# Power-Sheet-2.net
KiCad netlist of a schematic drawn in Altium Designer
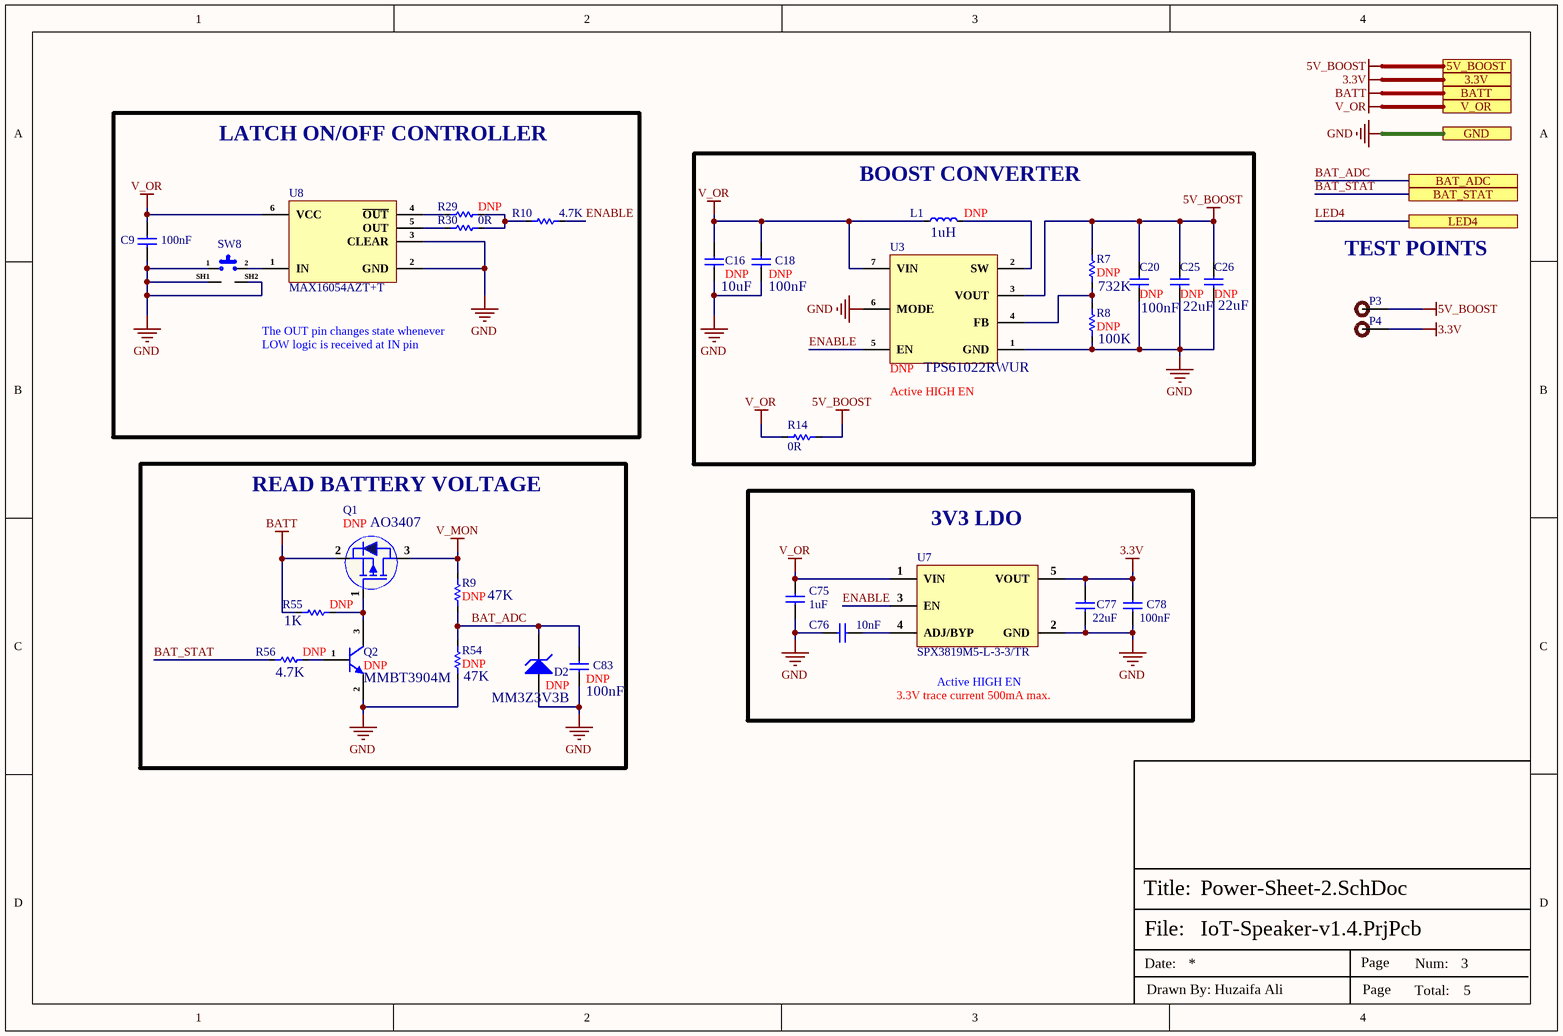
[diagram p0: Power-Sheet-2.SchDoc]

(export (version "E")
  (design (tool "Eeschema 10.0.6"))
  (components
    (comp (ref "C9")
      (value "100nF")
      (footprint "Cap-0402")
      (description "CAP CER 0.1UF 25V X5R 0402")
      (fields
        (field (name "MANUFACTURER") "Yageo")
        (field (name "MANUFACTURER PART NUMBER") "CC0402KRX5R8BB104")
      )
      (libsource (lib "eSpark_centralized_Library(2022)") (part "CC0402KRX5R8BB104"))
    )
    (comp (ref "C16")
      (value "DNP")
      (footprint "Cap-0805")
      (description "CAP CER 10UF 25V X5R 0805")
      (fields
        (field (name "MANUFACTURER") "Yageo")
        (field (name "MANUFACTURER PART NUMBER") "CC0805KKX5R8BB106")
      )
      (libsource (lib "eSpark_centralized_Library(2022)") (part "CC0805KKX5R8BB106"))
    )
    (comp (ref "C18")
      (value "DNP")
      (footprint "Cap-0402")
      (description "CAP CER 0.1UF 25V X5R 0402")
      (fields
        (field (name "MANUFACTURER") "Yageo")
        (field (name "MANUFACTURER PART NUMBER") "CC0402KRX5R8BB104")
      )
      (libsource (lib "eSpark_centralized_Library(2022)") (part "CC0402KRX5R8BB104"))
    )
    (comp (ref "C20")
      (value "DNP")
      (footprint "Cap-0402")
      (description "CAP CER 0.1UF 25V X5R 0402")
      (fields
        (field (name "MANUFACTURER") "Yageo")
        (field (name "MANUFACTURER PART NUMBER") "CC0402KRX5R8BB104")
      )
      (libsource (lib "eSpark_centralized_Library(2022)") (part "CC0402KRX5R8BB104"))
    )
    (comp (ref "C25")
      (value "DNP")
      (footprint "Cap-0603")
      (description "CAP CER 22UF 10V X5R 0603")
      (fields
        (field (name "MANUFACTURER") "Yageo")
        (field (name "MANUFACTURER PART NUMBER") "CC0603MRX5R6BB226")
      )
      (libsource (lib "eSpark_centralized_Library(2022)") (part "CC0603MRX5R6BB226"))
    )
    (comp (ref "C26")
      (value "DNP")
      (footprint "Cap-0603")
      (description "CAP CER 22UF 10V X5R 0603")
      (fields
        (field (name "MANUFACTURER") "Yageo")
        (field (name "MANUFACTURER PART NUMBER") "CC0603MRX5R6BB226")
      )
      (libsource (lib "eSpark_centralized_Library(2022)") (part "CC0603MRX5R6BB226"))
    )
    (comp (ref "C75")
      (value "1uF")
      (footprint "Cap-0603")
      (description "CAP CER 1UF 25V X5R 0603")
      (fields
        (field (name "MANUFACTURER") "Yageo")
        (field (name "MANUFACTURER PART NUMBER") "CC0603KRX5R8BB105")
      )
      (libsource (lib "eSpark_centralized_Library(2022)") (part "CC0603KRX5R8BB105"))
    )
    (comp (ref "C76")
      (value "10nF")
      (footprint "Cap-0603")
      (description "CAP CER 10000PF 50V C0G/NPO 0603")
      (fields
        (field (name "MANUFACTURER") "Yageo")
        (field (name "MANUFACTURER PART NUMBER") "CC0603JRNPO9BN103")
      )
      (libsource (lib "eSpark_centralized_Library(2022)") (part "CC0603JRNPO9BN103"))
    )
    (comp (ref "C77")
      (value "22uF")
      (footprint "Cap-0603")
      (description "CAP CER 22UF 10V X5R 0603")
      (fields
        (field (name "MANUFACTURER") "Yageo")
        (field (name "MANUFACTURER PART NUMBER") "CC0603MRX5R6BB226")
      )
      (libsource (lib "eSpark_centralized_Library(2022)") (part "CC0603MRX5R6BB226"))
    )
    (comp (ref "C78")
      (value "100nF")
      (footprint "Cap-0402")
      (description "CAP CER 0.1UF 25V X5R 0402")
      (fields
        (field (name "MANUFACTURER") "Yageo")
        (field (name "MANUFACTURER PART NUMBER") "CC0402KRX5R8BB104")
      )
      (libsource (lib "eSpark_centralized_Library(2022)") (part "CC0402KRX5R8BB104"))
    )
    (comp (ref "C83")
      (value "DNP")
      (footprint "Cap-0402")
      (description "CAP CER 0.1UF 25V X5R 0402")
      (fields
        (field (name "MANUFACTURER") "Yageo")
        (field (name "MANUFACTURER PART NUMBER") "CC0402KRX5R8BB104")
      )
      (libsource (lib "eSpark_centralized_Library(2022)") (part "CC0402KRX5R8BB104"))
    )
    (comp (ref "D2")
      (value "DNP")
      (footprint "SOD323F")
      (description "DIODE ZENER 3.3V 200MW SOD323F")
      (fields
        (field (name "MANUFACTURER") "ON Semiconductor / Fairchild")
        (field (name "MANUFACTURER PART NUMBER") "MM3Z3V3B")
      )
      (libsource (lib "eSpark_centralized_Library(2022)") (part "MM3Z3V3B"))
    )
    (comp (ref "L1")
      (value "DNP")
      (footprint "MPIT6045-1R0N-LF")
      (description "5.15A 1uH ±30% SMD Power Inductors ROHS")
      (fields
        (field (name "MANUFACTURER") "microgate")
        (field (name "MANUFACTURER PART NUMBER") "MPIT6045-1R0N-LF")
      )
      (libsource (lib "eSpark_centralized_Library(2022)") (part "MPIT6045-1R0N-LF"))
    )
    (comp (ref "P3")
      (value "TEST POINT")
      (footprint "Test-point")
      (description "Test Point ON")
      (libsource (lib "eSpark_centralized_Library(2022)") (part "TEST POINT"))
    )
    (comp (ref "P4")
      (value "TEST POINT")
      (footprint "Test-point")
      (description "Test Point ON")
      (libsource (lib "eSpark_centralized_Library(2022)") (part "TEST POINT"))
    )
    (comp (ref "Q1")
      (value "DNP")
      (footprint "SOT-23")
      (description "30V 4.1A 60mΩ@10V,4.1A 350mW 3V@250uA P Channel SOT-23 MOSFETs ROHS")
      (fields
        (field (name "MANUFACTURER") "Guangdong Hottech")
        (field (name "MANUFACTURER PART NUMBER") "AO3407")
      )
      (libsource (lib "eSpark_centralized_Library(2022)") (part "AO3407"))
    )
    (comp (ref "Q2")
      (value "DNP")
      (footprint "SOT-723")
      (fields
        (field (name "MANUFACTURER") "TECH PUBLIC")
        (field (name "MANUFACTURER PART NUMBER") "MMBT3904M")
        (field (name "LCSC PART NUMBER") "C2923360")
      )
      (libsource (lib "eSpark_centralized_Library(2022)") (part "MMBT3904M"))
    )
    (comp (ref "R7")
      (value "DNP")
      (footprint "Res-0402")
      (description "±1% 732kΩ 0402 Chip Resistor - Surface Mount ROHS")
      (fields
        (field (name "MANUFACTURER") "FOJAN")
        (field (name "MANUFACTURER PART NUMBER") "FRC0402F7323TS")
      )
      (libsource (lib "eSpark_centralized_Library(2022)") (part "FRC0402F7323TS"))
    )
    (comp (ref "R8")
      (value "DNP")
      (footprint "Res-0603")
      (description "RES SMD 100K OHM 0.1% 1/10W 0603")
      (fields
        (field (name "MANUFACTURER") "Yageo")
        (field (name "MANUFACTURER PART NUMBER") "RT0603BRD07100KL")
      )
      (libsource (lib "eSpark_centralized_Library(2022)") (part "RT0603BRD07100KL"))
    )
    (comp (ref "R9")
      (value "DNP")
      (footprint "Res-0603")
      (description "RES 47K OHM 5% 1/10W 0603")
      (fields
        (field (name "MANUFACTURER") "Yageo")
        (field (name "MANUFACTURER PART NUMBER") "RC0603JR-0747KL")
      )
      (libsource (lib "eSpark_centralized_Library(2022)") (part "RC0603JR-0747KL"))
    )
    (comp (ref "R10")
      (value "4.7K")
      (footprint "Res-0603")
      (description "RES SMD 4.7K OHM 5% 1/10W 0603")
      (fields
        (field (name "MANUFACTURER") "Yageo")
        (field (name "MANUFACTURER PART NUMBER") "RC0603JR-074K7L")
      )
      (libsource (lib "eSpark Libraries") (part "RC0603JR-074K7L"))
    )
    (comp (ref "R14")
      (value "0R")
      (footprint "Res-0603")
      (description "RES 0 OHM JUMPER 1/10W 0603")
      (fields
        (field (name "MANUFACTURER") "Yageo")
        (field (name "MANUFACTURER PART NUMBER") "RC0603JR-070RL")
      )
      (libsource (lib "eSpark Libraries") (part "RC0603JR-070RL"))
    )
    (comp (ref "R29")
      (value "DNP")
      (footprint "Res-0603")
      (description "RES SMD 0R, 1%, 0.1W, 0603")
      (fields
        (field (name "MANUFACTURER") "Yageo")
        (field (name "MANUFACTURER PART NUMBER") "RC0603FR-070RL")
      )
      (libsource (lib "eSpark Libraries") (part "RC0603FR-070RL"))
    )
    (comp (ref "R30")
      (value "0R")
      (footprint "Res-0603")
      (description "RES SMD 0R, 1%, 0.1W, 0603")
      (fields
        (field (name "MANUFACTURER") "Yageo")
        (field (name "MANUFACTURER PART NUMBER") "RC0603FR-070RL")
      )
      (libsource (lib "eSpark Libraries") (part "RC0603FR-070RL"))
    )
    (comp (ref "R54")
      (value "DNP")
      (footprint "Res-0603")
      (description "RES 47K OHM 5% 1/10W 0603")
      (fields
        (field (name "MANUFACTURER") "Yageo")
        (field (name "MANUFACTURER PART NUMBER") "RC0603JR-0747KL")
      )
      (libsource (lib "eSpark_centralized_Library(2022)") (part "RC0603JR-0747KL"))
    )
    (comp (ref "R55")
      (value "DNP")
      (footprint "Res-0603")
      (description "RES SMD 1K OHM 1% 1/10W 0603")
      (fields
        (field (name "MANUFACTURER") "Yageo")
        (field (name "MANUFACTURER PART NUMBER") "RC0603FR-071KL")
      )
      (libsource (lib "eSpark_centralized_Library(2022)") (part "RC0603FR-071KL"))
    )
    (comp (ref "R56")
      (value "DNP")
      (footprint "Res-0603")
      (description "RES SMD 4.7K OHM 5% 1/10W 0603")
      (fields
        (field (name "MANUFACTURER") "Yageo")
        (field (name "MANUFACTURER PART NUMBER") "RC0603JR-074K7L")
      )
      (libsource (lib "eSpark_centralized_Library(2022)") (part "RC0603JR-074K7L"))
    )
    (comp (ref "SW8")
      (value "TS-1087E-B3D2")
      (footprint "TS-1087E-B3D2")
      (description "Plugin-4P,7.7x3.5mm Tactile Switches ROHS")
      (fields (field (name "MANUFACTURER") "Yuandi") (field (name "LCSC PART NUMBER") "C541963"))
      (libsource (lib "eSpark Libraries") (part "TS-1087E-B3D2"))
    )
    (comp (ref "U3")
      (value "DNP")
      (footprint "7-VQFN-HR (2x2)")
      (description "8-A boost converter with 0.5-V ultra-low input voltage 7-VQFN-HR -40 to 125")
      (fields
        (field (name "MANUFACTURER") "Texas Instruments")
        (field (name "MANUFACTURER PART NUMBER") "TPS61022RWUR")
      )
      (libsource (lib "Centralize") (part "TPS61022RWUR"))
    )
    (comp (ref "U7")
      (value "SPX3819M5-L-3-3/TR")
      (footprint "SOT-23-5")
      (description "SPX3819 Series 3.3 V 500 mA Fixed Output SMT LDO Regulator - SOT-23-5")
      (fields (field (name "MANUFACTURER") "MaxLinear") (field (name "LCSC PART NUMBER") "C9055"))
      (libsource (lib "eSpark_centralized_Library(2022)") (part "SPX3819M5-L-3-3/TR"))
    )
    (comp (ref "U8")
      (value "MAX16054AZT+T")
      (footprint "TSOT-23-6")
      (description "IC CNTRLR ON/OFF W/DEB TSOT23-6")
      (fields (field (name "MANUFACTURER") "Maxim") (field (name "LCSC PART NUMBER") "C79401"))
      (libsource (lib "eSpark_centralized_Library(2022)") (part "MAX16054AZT+T"))
    )
  )
  (nets
    (net (code "1") (name "/BAT_ADC") (class "Default")
      (node (ref "C83") (pin "2") (pinfunction "2_2") (pintype "passive"))
      (node (ref "D2") (pin "2") (pinfunction "K_2") (pintype "passive"))
      (node (ref "R54") (pin "2") (pinfunction "2_2") (pintype "passive"))
      (node (ref "R9") (pin "1") (pinfunction "1_1") (pintype "passive"))
    )
    (net (code "2") (name "/BAT_STAT") (class "Default")
      (node (ref "R56") (pin "1") (pinfunction "1_1") (pintype "passive"))
    )
    (net (code "3") (name "/ENABLE") (class "Default")
      (node (ref "R10") (pin "2") (pinfunction "2_2") (pintype "passive"))
      (node (ref "U3") (pin "5") (pinfunction "EN_5") (pintype "passive"))
      (node (ref "U7") (pin "3") (pinfunction "EN_3") (pintype "passive"))
    )
    (net (code "5") (name "3.3V") (class "Default")
      (node (ref "C77") (pin "2") (pinfunction "2_2") (pintype "passive"))
      (node (ref "C78") (pin "2") (pinfunction "2_2") (pintype "passive"))
      (node (ref "P4") (pin "1") (pinfunction "1_1") (pintype "passive"))
      (node (ref "U7") (pin "5") (pinfunction "VOUT_5") (pintype "passive"))
    )
    (net (code "6") (name "5V_BOOST") (class "Default")
      (node (ref "C20") (pin "2") (pinfunction "2_2") (pintype "passive"))
      (node (ref "C25") (pin "2") (pinfunction "2_2") (pintype "passive"))
      (node (ref "C26") (pin "2") (pinfunction "2_2") (pintype "passive"))
      (node (ref "P3") (pin "1") (pinfunction "1_1") (pintype "passive"))
      (node (ref "R14") (pin "2") (pinfunction "2_2") (pintype "passive"))
      (node (ref "R7") (pin "2") (pinfunction "2_2") (pintype "passive"))
      (node (ref "U3") (pin "3") (pinfunction "VOUT_3") (pintype "passive"))
    )
    (net (code "7") (name "BATT") (class "Default")
      (node (ref "Q1") (pin "2") (pinfunction "S_2") (pintype "passive"))
      (node (ref "R55") (pin "1") (pinfunction "1_1") (pintype "passive"))
    )
    (net (code "8") (name "GND") (class "Default")
      (node (ref "C16") (pin "1") (pinfunction "1_1") (pintype "passive"))
      (node (ref "C18") (pin "1") (pinfunction "1_1") (pintype "passive"))
      (node (ref "C20") (pin "1") (pinfunction "1_1") (pintype "passive"))
      (node (ref "C25") (pin "1") (pinfunction "1_1") (pintype "passive"))
      (node (ref "C26") (pin "1") (pinfunction "1_1") (pintype "passive"))
      (node (ref "C75") (pin "1") (pinfunction "1_1") (pintype "passive"))
      (node (ref "C76") (pin "1") (pinfunction "1_1") (pintype "passive"))
      (node (ref "C77") (pin "1") (pinfunction "1_1") (pintype "passive"))
      (node (ref "C78") (pin "1") (pinfunction "1_1") (pintype "passive"))
      (node (ref "C83") (pin "1") (pinfunction "1_1") (pintype "passive"))
      (node (ref "C9") (pin "1") (pinfunction "1_1") (pintype "passive"))
      (node (ref "D2") (pin "1") (pinfunction "A_1") (pintype "passive"))
      (node (ref "Q2") (pin "2") (pinfunction "E_2") (pintype "passive"))
      (node (ref "R54") (pin "1") (pinfunction "1_1") (pintype "passive"))
      (node (ref "R8") (pin "1") (pinfunction "1_1") (pintype "passive"))
      (node (ref "SW8") (pin "1") (pinfunction "1_1") (pintype "passive"))
      (node (ref "SW8") (pin "SH1") (pinfunction "SH1_SH1") (pintype "passive"))
      (node (ref "SW8") (pin "SH2") (pinfunction "SH2_SH2") (pintype "passive"))
      (node (ref "U3") (pin "1") (pinfunction "GND_1") (pintype "passive"))
      (node (ref "U3") (pin "6") (pinfunction "MODE_6") (pintype "passive"))
      (node (ref "U7") (pin "2") (pinfunction "GND_2") (pintype "passive"))
      (node (ref "U8") (pin "2") (pinfunction "GND_2") (pintype "passive"))
      (node (ref "U8") (pin "3") (pinfunction "CLEAR_3") (pintype "passive"))
    )
    (net (code "9") (name "Net-(Q1-G)") (class "Default")
      (node (ref "Q1") (pin "1") (pinfunction "G_1") (pintype "passive"))
      (node (ref "Q2") (pin "3") (pinfunction "C_3") (pintype "passive"))
      (node (ref "R55") (pin "2") (pinfunction "2_2") (pintype "passive"))
    )
    (net (code "10") (name "Net-(Q2-B)") (class "Default")
      (node (ref "Q2") (pin "1") (pinfunction "B_1") (pintype "passive"))
      (node (ref "R56") (pin "2") (pinfunction "2_2") (pintype "passive"))
    )
    (net (code "11") (name "Net-(R10-Pad1)") (class "Default")
      (node (ref "R10") (pin "1") (pinfunction "1_1") (pintype "passive"))
      (node (ref "R29") (pin "2") (pinfunction "2_2") (pintype "passive"))
      (node (ref "R30") (pin "2") (pinfunction "2_2") (pintype "passive"))
    )
    (net (code "12") (name "Net-(U3-FB)") (class "Default")
      (node (ref "R7") (pin "1") (pinfunction "1_1") (pintype "passive"))
      (node (ref "R8") (pin "2") (pinfunction "2_2") (pintype "passive"))
      (node (ref "U3") (pin "4") (pinfunction "FB_4") (pintype "passive"))
    )
    (net (code "13") (name "Net-(U3-SW)") (class "Default")
      (node (ref "L1") (pin "2") (pinfunction "2_2") (pintype "passive"))
      (node (ref "U3") (pin "2") (pinfunction "SW_2") (pintype "passive"))
    )
    (net (code "14") (name "Net-(U7-ADJ{slash}BYP)") (class "Default")
      (node (ref "C76") (pin "2") (pinfunction "2_2") (pintype "passive"))
      (node (ref "U7") (pin "4") (pinfunction "ADJ/BYP_4") (pintype "passive"))
    )
    (net (code "15") (name "Net-(U8-IN)") (class "Default")
      (node (ref "SW8") (pin "2") (pinfunction "2_2") (pintype "passive"))
      (node (ref "U8") (pin "1") (pinfunction "IN_1") (pintype "passive"))
    )
    (net (code "16") (name "Net-(U8-OUT)") (class "Default")
      (node (ref "R30") (pin "1") (pinfunction "1_1") (pintype "passive"))
      (node (ref "U8") (pin "5") (pinfunction "OUT_5") (pintype "passive"))
    )
    (net (code "17") (name "Net-(U8-~{OUT})") (class "Default")
      (node (ref "R29") (pin "1") (pinfunction "1_1") (pintype "passive"))
      (node (ref "U8") (pin "4") (pinfunction "~{OUT}_4") (pintype "passive"))
    )
    (net (code "18") (name "V_MON") (class "Default")
      (node (ref "Q1") (pin "3") (pinfunction "D_3") (pintype "passive"))
      (node (ref "R9") (pin "2") (pinfunction "2_2") (pintype "passive"))
    )
    (net (code "19") (name "V_OR") (class "Default")
      (node (ref "C16") (pin "2") (pinfunction "2_2") (pintype "passive"))
      (node (ref "C18") (pin "2") (pinfunction "2_2") (pintype "passive"))
      (node (ref "C75") (pin "2") (pinfunction "2_2") (pintype "passive"))
      (node (ref "C9") (pin "2") (pinfunction "2_2") (pintype "passive"))
      (node (ref "L1") (pin "1") (pinfunction "1_1") (pintype "passive"))
      (node (ref "R14") (pin "1") (pinfunction "1_1") (pintype "passive"))
      (node (ref "U3") (pin "7") (pinfunction "VIN_7") (pintype "passive"))
      (node (ref "U7") (pin "1") (pinfunction "VIN_1") (pintype "passive"))
      (node (ref "U8") (pin "6") (pinfunction "VCC_6") (pintype "passive"))
    )
  )
)
